# control_FET.net
KiCad netlist of a schematic drawn in EAGLE
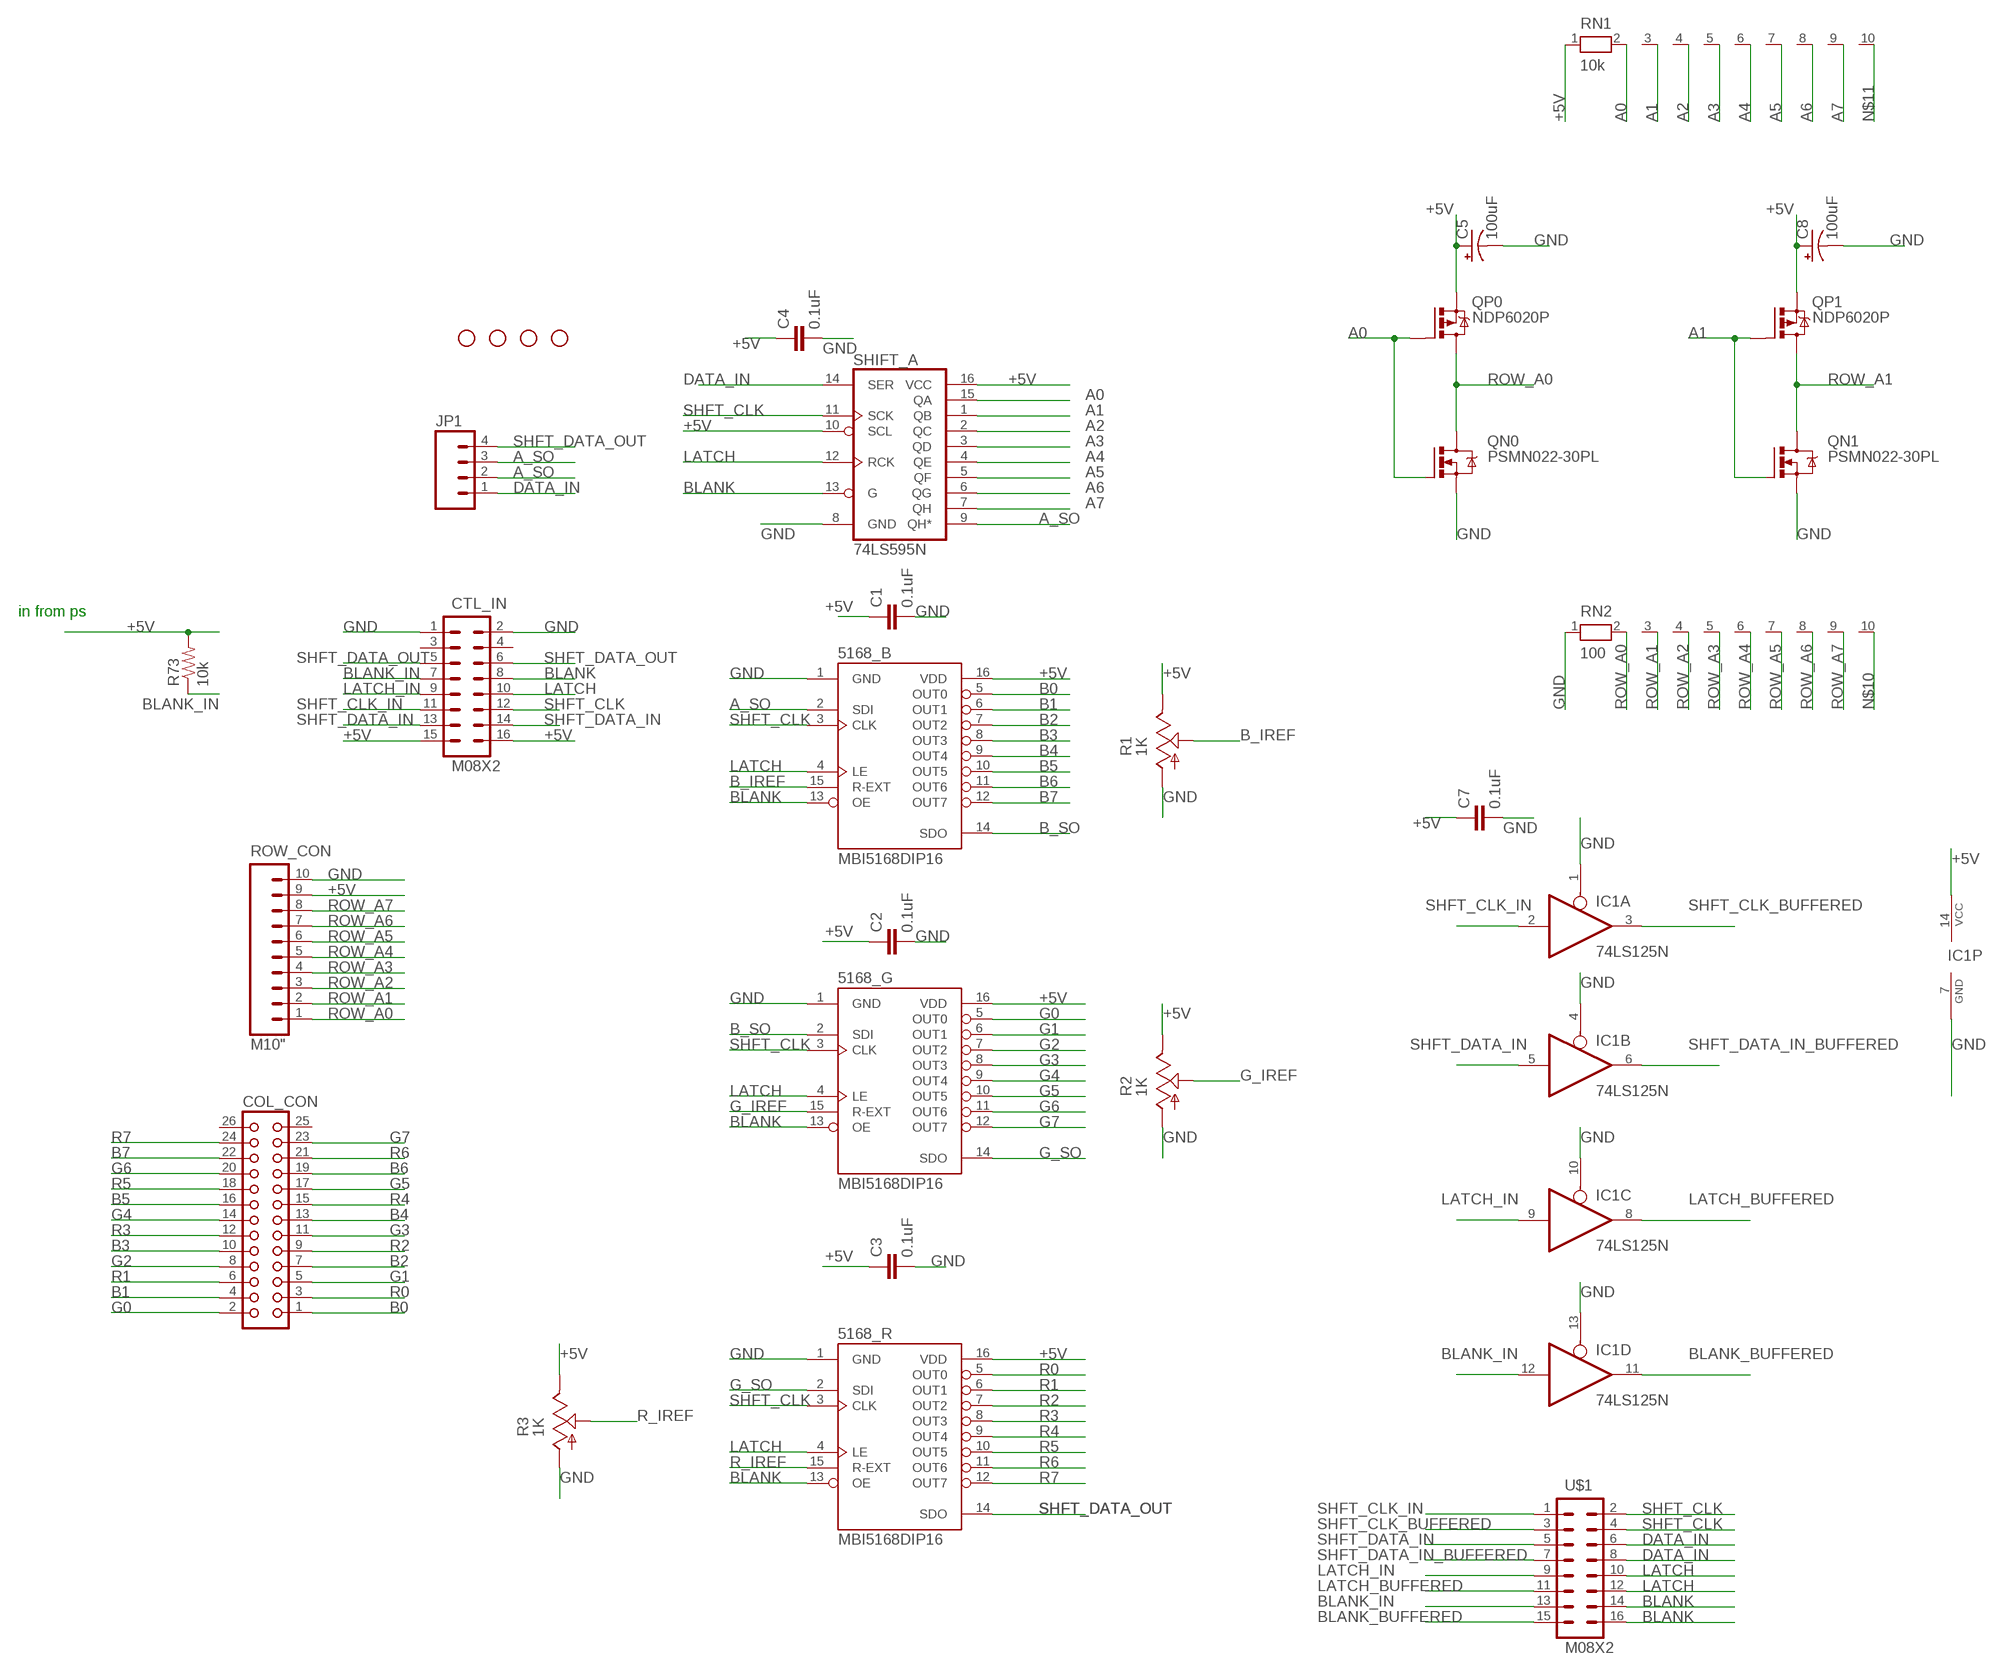
[diagram p0: schematic, sheet 1, part 1 of 2]
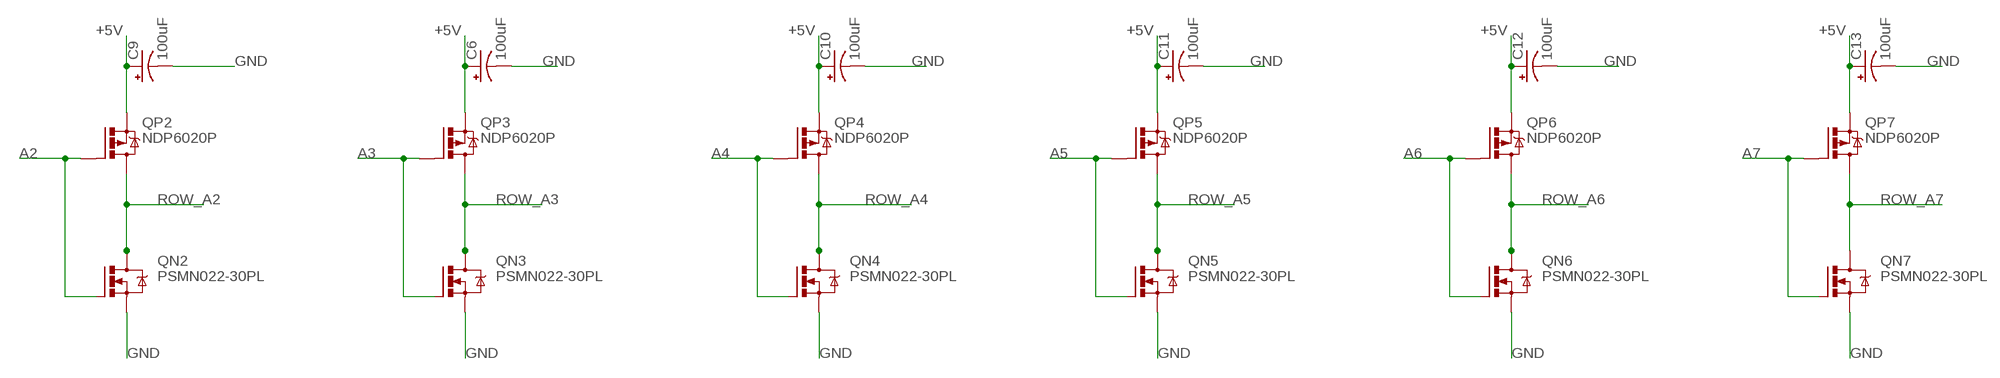
[diagram p1: schematic, sheet 1, part 2 of 2]

(export (version "E")
  (design (tool "Eeschema 10.0.6"))
  (components
    (comp (ref "5168_B")
      (value "MBI5168DIP16")
      (footprint "eagle-import:DIL16")
      (libsource (lib "eagle-import") (part "MBI5168DIP16"))
    )
    (comp (ref "5168_G")
      (value "MBI5168DIP16")
      (footprint "eagle-import:DIL16")
      (libsource (lib "eagle-import") (part "MBI5168DIP16"))
    )
    (comp (ref "5168_R")
      (value "MBI5168DIP16")
      (footprint "eagle-import:DIL16")
      (libsource (lib "eagle-import") (part "MBI5168DIP16"))
    )
    (comp (ref "C1")
      (value "0.1uF")
      (footprint "eagle-import:C2.5-3")
      (libsource (lib "eagle-import") (part "C2,5-3"))
    )
    (comp (ref "C2")
      (value "0.1uF")
      (footprint "eagle-import:C2.5-3")
      (libsource (lib "eagle-import") (part "C2,5-3"))
    )
    (comp (ref "C3")
      (value "0.1uF")
      (footprint "eagle-import:C2.5-3")
      (libsource (lib "eagle-import") (part "C2,5-3"))
    )
    (comp (ref "C4")
      (value "0.1uF")
      (footprint "eagle-import:C2.5-3")
      (libsource (lib "eagle-import") (part "C2,5-3"))
    )
    (comp (ref "C5")
      (value "100uF")
      (footprint "eagle-import:CPOL-RADIAL-100UF-25V")
      (libsource (lib "eagle-import") (part "CAP_POLPTH1"))
    )
    (comp (ref "C6")
      (value "100uF")
      (footprint "eagle-import:CPOL-RADIAL-100UF-25V")
      (libsource (lib "eagle-import") (part "CAP_POLPTH1"))
    )
    (comp (ref "C7")
      (value "0.1uF")
      (footprint "eagle-import:C2.5-3")
      (libsource (lib "eagle-import") (part "C2,5-3"))
    )
    (comp (ref "C8")
      (value "100uF")
      (footprint "eagle-import:CPOL-RADIAL-100UF-25V")
      (libsource (lib "eagle-import") (part "CAP_POLPTH1"))
    )
    (comp (ref "C9")
      (value "100uF")
      (footprint "eagle-import:CPOL-RADIAL-100UF-25V")
      (libsource (lib "eagle-import") (part "CAP_POLPTH1"))
    )
    (comp (ref "C10")
      (value "100uF")
      (footprint "eagle-import:CPOL-RADIAL-100UF-25V")
      (libsource (lib "eagle-import") (part "CAP_POLPTH1"))
    )
    (comp (ref "C11")
      (value "100uF")
      (footprint "eagle-import:CPOL-RADIAL-100UF-25V")
      (libsource (lib "eagle-import") (part "CAP_POLPTH1"))
    )
    (comp (ref "C12")
      (value "100uF")
      (footprint "eagle-import:CPOL-RADIAL-100UF-25V")
      (libsource (lib "eagle-import") (part "CAP_POLPTH1"))
    )
    (comp (ref "C13")
      (value "100uF")
      (footprint "eagle-import:CPOL-RADIAL-100UF-25V")
      (libsource (lib "eagle-import") (part "CAP_POLPTH1"))
    )
    (comp (ref "COL_CON")
      (value "CON26")
      (footprint "eagle-import:CON26")
      (libsource (lib "eagle-import") (part "CON26"))
    )
    (comp (ref "CTL_IN")
      (value "M08X2")
      (footprint "eagle-import:2X8")
      (libsource (lib "eagle-import") (part "M08X2"))
    )
    (comp (ref "IC1")
      (value "74LS125N")
      (footprint "eagle-import:DIL14")
      (libsource (lib "eagle-import") (part "74125NLS"))
    )
    (comp (ref "JP1")
      (value "M04PTH")
      (footprint "eagle-import:1X04")
      (libsource (lib "eagle-import") (part "M04PTH"))
    )
    (comp (ref "QN0")
      (value "PSMN022-30PL")
      (footprint "eagle-import:TO220BV")
      (libsource (lib "eagle-import") (part "IRF520"))
    )
    (comp (ref "QN1")
      (value "PSMN022-30PL")
      (footprint "eagle-import:TO220BV")
      (libsource (lib "eagle-import") (part "IRF520"))
    )
    (comp (ref "QN2")
      (value "PSMN022-30PL")
      (footprint "eagle-import:TO220BV")
      (libsource (lib "eagle-import") (part "IRF520"))
    )
    (comp (ref "QN3")
      (value "PSMN022-30PL")
      (footprint "eagle-import:TO220BV")
      (libsource (lib "eagle-import") (part "IRF520"))
    )
    (comp (ref "QN4")
      (value "PSMN022-30PL")
      (footprint "eagle-import:TO220BV")
      (libsource (lib "eagle-import") (part "IRF520"))
    )
    (comp (ref "QN5")
      (value "PSMN022-30PL")
      (footprint "eagle-import:TO220BV")
      (libsource (lib "eagle-import") (part "IRF520"))
    )
    (comp (ref "QN6")
      (value "PSMN022-30PL")
      (footprint "eagle-import:TO220BV")
      (libsource (lib "eagle-import") (part "IRF520"))
    )
    (comp (ref "QN7")
      (value "PSMN022-30PL")
      (footprint "eagle-import:TO220BV")
      (libsource (lib "eagle-import") (part "IRF520"))
    )
    (comp (ref "QP0")
      (value "NDP6020P")
      (footprint "eagle-import:TO220BV")
      (libsource (lib "eagle-import") (part "IRF9530"))
    )
    (comp (ref "QP1")
      (value "NDP6020P")
      (footprint "eagle-import:TO220BV")
      (libsource (lib "eagle-import") (part "IRF9530"))
    )
    (comp (ref "QP2")
      (value "NDP6020P")
      (footprint "eagle-import:TO220BV")
      (libsource (lib "eagle-import") (part "IRF9530"))
    )
    (comp (ref "QP3")
      (value "NDP6020P")
      (footprint "eagle-import:TO220BV")
      (libsource (lib "eagle-import") (part "IRF9530"))
    )
    (comp (ref "QP4")
      (value "NDP6020P")
      (footprint "eagle-import:TO220BV")
      (libsource (lib "eagle-import") (part "IRF9530"))
    )
    (comp (ref "QP5")
      (value "NDP6020P")
      (footprint "eagle-import:TO220BV")
      (libsource (lib "eagle-import") (part "IRF9530"))
    )
    (comp (ref "QP6")
      (value "NDP6020P")
      (footprint "eagle-import:TO220BV")
      (libsource (lib "eagle-import") (part "IRF9530"))
    )
    (comp (ref "QP7")
      (value "NDP6020P")
      (footprint "eagle-import:TO220BV")
      (libsource (lib "eagle-import") (part "IRF9530"))
    )
    (comp (ref "R1")
      (value "1K")
      (footprint "eagle-import:CA6V")
      (libsource (lib "eagle-import") (part "TRIM_US-CA6V"))
    )
    (comp (ref "R2")
      (value "1K")
      (footprint "eagle-import:CA6V")
      (libsource (lib "eagle-import") (part "TRIM_US-CA6V"))
    )
    (comp (ref "R3")
      (value "1K")
      (footprint "eagle-import:CA6V")
      (libsource (lib "eagle-import") (part "TRIM_US-CA6V"))
    )
    (comp (ref "R73")
      (value "10k")
      (footprint "eagle-import:0207_10")
      (libsource (lib "eagle-import") (part "R-US_0207/10"))
    )
    (comp (ref "RN1")
      (value "10k")
      (footprint "eagle-import:RN-10")
      (libsource (lib "eagle-import") (part "RN09"))
    )
    (comp (ref "RN2")
      (value "100")
      (footprint "eagle-import:RN-10")
      (libsource (lib "eagle-import") (part "RN09"))
    )
    (comp (ref "ROW_CON")
      (value "M10\"")
      (footprint "eagle-import:1X10")
      (libsource (lib "eagle-import") (part "M10{dblquote}"))
    )
    (comp (ref "SHIFT_A")
      (value "74LS595N")
      (footprint "eagle-import:DIL16")
      (libsource (lib "eagle-import") (part "74595NLS"))
    )
    (comp (ref "STANDOFF1")
      (value "STAND-OFF")
      (footprint "eagle-import:STAND-OFF")
      (libsource (lib "eagle-import") (part "STAND-OFF"))
    )
    (comp (ref "STANDOFF2")
      (value "STAND-OFF")
      (footprint "eagle-import:STAND-OFF")
      (libsource (lib "eagle-import") (part "STAND-OFF"))
    )
    (comp (ref "STANDOFF3")
      (value "STAND-OFF")
      (footprint "eagle-import:STAND-OFF")
      (libsource (lib "eagle-import") (part "STAND-OFF"))
    )
    (comp (ref "STANDOFF4")
      (value "STAND-OFF")
      (footprint "eagle-import:STAND-OFF")
      (libsource (lib "eagle-import") (part "STAND-OFF"))
    )
    (comp (ref "U$1")
      (value "M08X2")
      (footprint "eagle-import:2X8")
      (libsource (lib "eagle-import") (part "M08X2"))
    )
  )
  (nets
    (net (code "1") (name "/+5V") (class "Default")
      (node (ref "5168_B") (pin "16") (pinfunction "VDD_16") (pintype "power_in"))
      (node (ref "5168_G") (pin "16") (pinfunction "VDD_16") (pintype "power_in"))
      (node (ref "5168_R") (pin "16") (pinfunction "VDD_16") (pintype "power_in"))
      (node (ref "C1") (pin "1") (pinfunction "1_1") (pintype "passive"))
      (node (ref "C10") (pin "1") (pinfunction "+_1") (pintype "passive"))
      (node (ref "C11") (pin "1") (pinfunction "+_1") (pintype "passive"))
      (node (ref "C12") (pin "1") (pinfunction "+_1") (pintype "passive"))
      (node (ref "C13") (pin "1") (pinfunction "+_1") (pintype "passive"))
      (node (ref "C2") (pin "1") (pinfunction "1_1") (pintype "passive"))
      (node (ref "C3") (pin "1") (pinfunction "1_1") (pintype "passive"))
      (node (ref "C4") (pin "1") (pinfunction "1_1") (pintype "passive"))
      (node (ref "C5") (pin "1") (pinfunction "+_1") (pintype "passive"))
      (node (ref "C6") (pin "1") (pinfunction "+_1") (pintype "passive"))
      (node (ref "C7") (pin "1") (pinfunction "1_1") (pintype "passive"))
      (node (ref "C8") (pin "1") (pinfunction "+_1") (pintype "passive"))
      (node (ref "C9") (pin "1") (pinfunction "+_1") (pintype "passive"))
      (node (ref "CTL_IN") (pin "15") (pinfunction "15_15") (pintype "passive"))
      (node (ref "CTL_IN") (pin "16") (pinfunction "16_16") (pintype "passive"))
      (node (ref "IC1") (pin "14") (pinfunction "VCC_14") (pintype "power_in"))
      (node (ref "QP0") (pin "S") (pinfunction "S_S") (pintype "passive"))
      (node (ref "QP1") (pin "S") (pinfunction "S_S") (pintype "passive"))
      (node (ref "QP2") (pin "S") (pinfunction "S_S") (pintype "passive"))
      (node (ref "QP3") (pin "S") (pinfunction "S_S") (pintype "passive"))
      (node (ref "QP4") (pin "S") (pinfunction "S_S") (pintype "passive"))
      (node (ref "QP5") (pin "S") (pinfunction "S_S") (pintype "passive"))
      (node (ref "QP6") (pin "S") (pinfunction "S_S") (pintype "passive"))
      (node (ref "QP7") (pin "S") (pinfunction "S_S") (pintype "passive"))
      (node (ref "R1") (pin "E") (pinfunction "E_E") (pintype "passive"))
      (node (ref "R2") (pin "E") (pinfunction "E_E") (pintype "passive"))
      (node (ref "R3") (pin "E") (pinfunction "E_E") (pintype "passive"))
      (node (ref "R73") (pin "2") (pinfunction "2_2") (pintype "passive"))
      (node (ref "RN1") (pin "1") (pinfunction "1_1") (pintype "passive"))
      (node (ref "ROW_CON") (pin "9") (pinfunction "9_9") (pintype "passive"))
      (node (ref "SHIFT_A") (pin "10") (pinfunction "SCL_10") (pintype "input"))
      (node (ref "SHIFT_A") (pin "16") (pinfunction "VCC_16") (pintype "power_in"))
    )
    (net (code "2") (name "/A0") (class "Default")
      (node (ref "QN0") (pin "G") (pinfunction "G_G") (pintype "passive"))
      (node (ref "QP0") (pin "G") (pinfunction "G_G") (pintype "passive"))
      (node (ref "RN1") (pin "2") (pinfunction "2_2") (pintype "passive"))
      (node (ref "SHIFT_A") (pin "15") (pinfunction "QA_15") (pintype "tri_state"))
    )
    (net (code "3") (name "/A1") (class "Default")
      (node (ref "QN1") (pin "G") (pinfunction "G_G") (pintype "passive"))
      (node (ref "QP1") (pin "G") (pinfunction "G_G") (pintype "passive"))
      (node (ref "RN1") (pin "3") (pinfunction "3_3") (pintype "passive"))
      (node (ref "SHIFT_A") (pin "1") (pinfunction "QB_1") (pintype "tri_state"))
    )
    (net (code "4") (name "/A2") (class "Default")
      (node (ref "QN2") (pin "G") (pinfunction "G_G") (pintype "passive"))
      (node (ref "QP2") (pin "G") (pinfunction "G_G") (pintype "passive"))
      (node (ref "RN1") (pin "4") (pinfunction "4_4") (pintype "passive"))
      (node (ref "SHIFT_A") (pin "2") (pinfunction "QC_2") (pintype "tri_state"))
    )
    (net (code "5") (name "/A3") (class "Default")
      (node (ref "QN3") (pin "G") (pinfunction "G_G") (pintype "passive"))
      (node (ref "QP3") (pin "G") (pinfunction "G_G") (pintype "passive"))
      (node (ref "RN1") (pin "5") (pinfunction "5_5") (pintype "passive"))
      (node (ref "SHIFT_A") (pin "3") (pinfunction "QD_3") (pintype "tri_state"))
    )
    (net (code "6") (name "/A4") (class "Default")
      (node (ref "QN4") (pin "G") (pinfunction "G_G") (pintype "passive"))
      (node (ref "QP4") (pin "G") (pinfunction "G_G") (pintype "passive"))
      (node (ref "RN1") (pin "6") (pinfunction "6_6") (pintype "passive"))
      (node (ref "SHIFT_A") (pin "4") (pinfunction "QE_4") (pintype "tri_state"))
    )
    (net (code "7") (name "/A5") (class "Default")
      (node (ref "QN5") (pin "G") (pinfunction "G_G") (pintype "passive"))
      (node (ref "QP5") (pin "G") (pinfunction "G_G") (pintype "passive"))
      (node (ref "RN1") (pin "7") (pinfunction "7_7") (pintype "passive"))
      (node (ref "SHIFT_A") (pin "5") (pinfunction "QF_5") (pintype "tri_state"))
    )
    (net (code "8") (name "/A6") (class "Default")
      (node (ref "QN6") (pin "G") (pinfunction "G_G") (pintype "passive"))
      (node (ref "QP6") (pin "G") (pinfunction "G_G") (pintype "passive"))
      (node (ref "RN1") (pin "8") (pinfunction "8_8") (pintype "passive"))
      (node (ref "SHIFT_A") (pin "6") (pinfunction "QG_6") (pintype "tri_state"))
    )
    (net (code "9") (name "/A7") (class "Default")
      (node (ref "QN7") (pin "G") (pinfunction "G_G") (pintype "passive"))
      (node (ref "QP7") (pin "G") (pinfunction "G_G") (pintype "passive"))
      (node (ref "RN1") (pin "9") (pinfunction "9_9") (pintype "passive"))
      (node (ref "SHIFT_A") (pin "7") (pinfunction "QH_7") (pintype "tri_state"))
    )
    (net (code "10") (name "/A_SO") (class "Default")
      (node (ref "5168_B") (pin "2") (pinfunction "SDI_2") (pintype "input"))
      (node (ref "JP1") (pin "2") (pinfunction "2_2") (pintype "passive"))
      (node (ref "JP1") (pin "3") (pinfunction "3_3") (pintype "passive"))
      (node (ref "SHIFT_A") (pin "9") (pinfunction "QH*_9") (pintype "tri_state"))
    )
    (net (code "11") (name "/B0") (class "Default")
      (node (ref "5168_B") (pin "5") (pinfunction "OUT0_5") (pintype "output"))
      (node (ref "COL_CON") (pin "1") (pinfunction "1_1") (pintype "passive"))
    )
    (net (code "12") (name "/B1") (class "Default")
      (node (ref "5168_B") (pin "6") (pinfunction "OUT1_6") (pintype "output"))
      (node (ref "COL_CON") (pin "4") (pinfunction "4_4") (pintype "passive"))
    )
    (net (code "13") (name "/B2") (class "Default")
      (node (ref "5168_B") (pin "7") (pinfunction "OUT2_7") (pintype "output"))
      (node (ref "COL_CON") (pin "7") (pinfunction "7_7") (pintype "passive"))
    )
    (net (code "14") (name "/B3") (class "Default")
      (node (ref "5168_B") (pin "8") (pinfunction "OUT3_8") (pintype "output"))
      (node (ref "COL_CON") (pin "10") (pinfunction "10_10") (pintype "passive"))
    )
    (net (code "15") (name "/B4") (class "Default")
      (node (ref "5168_B") (pin "9") (pinfunction "OUT4_9") (pintype "output"))
      (node (ref "COL_CON") (pin "13") (pinfunction "13_13") (pintype "passive"))
    )
    (net (code "16") (name "/B5") (class "Default")
      (node (ref "5168_B") (pin "10") (pinfunction "OUT5_10") (pintype "output"))
      (node (ref "COL_CON") (pin "16") (pinfunction "16_16") (pintype "passive"))
    )
    (net (code "17") (name "/B6") (class "Default")
      (node (ref "5168_B") (pin "11") (pinfunction "OUT6_11") (pintype "output"))
      (node (ref "COL_CON") (pin "19") (pinfunction "19_19") (pintype "passive"))
    )
    (net (code "18") (name "/B7") (class "Default")
      (node (ref "5168_B") (pin "12") (pinfunction "OUT7_12") (pintype "output"))
      (node (ref "COL_CON") (pin "22") (pinfunction "22_22") (pintype "passive"))
    )
    (net (code "19") (name "/BLANK") (class "Default")
      (node (ref "5168_B") (pin "13") (pinfunction "OE_13") (pintype "input"))
      (node (ref "5168_G") (pin "13") (pinfunction "OE_13") (pintype "input"))
      (node (ref "5168_R") (pin "13") (pinfunction "OE_13") (pintype "input"))
      (node (ref "CTL_IN") (pin "8") (pinfunction "8_8") (pintype "passive"))
      (node (ref "SHIFT_A") (pin "13") (pinfunction "G_13") (pintype "input"))
      (node (ref "U$1") (pin "14") (pinfunction "14_14") (pintype "passive"))
      (node (ref "U$1") (pin "16") (pinfunction "16_16") (pintype "passive"))
    )
    (net (code "20") (name "/BLANK_BUFFERED") (class "Default")
      (node (ref "IC1") (pin "11") (pinfunction "O_11") (pintype "tri_state"))
      (node (ref "U$1") (pin "15") (pinfunction "15_15") (pintype "passive"))
    )
    (net (code "21") (name "/BLANK_IN") (class "Default")
      (node (ref "CTL_IN") (pin "7") (pinfunction "7_7") (pintype "passive"))
      (node (ref "IC1") (pin "12") (pinfunction "I_12") (pintype "input"))
      (node (ref "R73") (pin "1") (pinfunction "1_1") (pintype "passive"))
      (node (ref "U$1") (pin "13") (pinfunction "13_13") (pintype "passive"))
    )
    (net (code "22") (name "/B_IREF") (class "Default")
      (node (ref "5168_B") (pin "15") (pinfunction "R-EXT_15") (pintype "input"))
      (node (ref "R1") (pin "S") (pinfunction "S_S") (pintype "passive"))
    )
    (net (code "23") (name "/B_SO") (class "Default")
      (node (ref "5168_B") (pin "14") (pinfunction "SDO_14") (pintype "output"))
      (node (ref "5168_G") (pin "2") (pinfunction "SDI_2") (pintype "input"))
    )
    (net (code "24") (name "/DATA_IN") (class "Default")
      (node (ref "JP1") (pin "1") (pinfunction "1_1") (pintype "passive"))
      (node (ref "SHIFT_A") (pin "14") (pinfunction "SER_14") (pintype "input"))
      (node (ref "U$1") (pin "6") (pinfunction "6_6") (pintype "passive"))
      (node (ref "U$1") (pin "8") (pinfunction "8_8") (pintype "passive"))
    )
    (net (code "25") (name "/G0") (class "Default")
      (node (ref "5168_G") (pin "5") (pinfunction "OUT0_5") (pintype "output"))
      (node (ref "COL_CON") (pin "2") (pinfunction "2_2") (pintype "passive"))
    )
    (net (code "26") (name "/G1") (class "Default")
      (node (ref "5168_G") (pin "6") (pinfunction "OUT1_6") (pintype "output"))
      (node (ref "COL_CON") (pin "5") (pinfunction "5_5") (pintype "passive"))
    )
    (net (code "27") (name "/G2") (class "Default")
      (node (ref "5168_G") (pin "7") (pinfunction "OUT2_7") (pintype "output"))
      (node (ref "COL_CON") (pin "8") (pinfunction "8_8") (pintype "passive"))
    )
    (net (code "28") (name "/G3") (class "Default")
      (node (ref "5168_G") (pin "8") (pinfunction "OUT3_8") (pintype "output"))
      (node (ref "COL_CON") (pin "11") (pinfunction "11_11") (pintype "passive"))
    )
    (net (code "29") (name "/G4") (class "Default")
      (node (ref "5168_G") (pin "9") (pinfunction "OUT4_9") (pintype "output"))
      (node (ref "COL_CON") (pin "14") (pinfunction "14_14") (pintype "passive"))
    )
    (net (code "30") (name "/G5") (class "Default")
      (node (ref "5168_G") (pin "10") (pinfunction "OUT5_10") (pintype "output"))
      (node (ref "COL_CON") (pin "17") (pinfunction "17_17") (pintype "passive"))
    )
    (net (code "31") (name "/G6") (class "Default")
      (node (ref "5168_G") (pin "11") (pinfunction "OUT6_11") (pintype "output"))
      (node (ref "COL_CON") (pin "20") (pinfunction "20_20") (pintype "passive"))
    )
    (net (code "32") (name "/G7") (class "Default")
      (node (ref "5168_G") (pin "12") (pinfunction "OUT7_12") (pintype "output"))
      (node (ref "COL_CON") (pin "23") (pinfunction "23_23") (pintype "passive"))
    )
    (net (code "33") (name "/GND") (class "Default")
      (node (ref "5168_B") (pin "1") (pinfunction "GND_1") (pintype "power_in"))
      (node (ref "5168_G") (pin "1") (pinfunction "GND_1") (pintype "power_in"))
      (node (ref "5168_R") (pin "1") (pinfunction "GND_1") (pintype "power_in"))
      (node (ref "C1") (pin "2") (pinfunction "2_2") (pintype "passive"))
      (node (ref "C10") (pin "2") (pinfunction "-_2") (pintype "passive"))
      (node (ref "C11") (pin "2") (pinfunction "-_2") (pintype "passive"))
      (node (ref "C12") (pin "2") (pinfunction "-_2") (pintype "passive"))
      (node (ref "C13") (pin "2") (pinfunction "-_2") (pintype "passive"))
      (node (ref "C2") (pin "2") (pinfunction "2_2") (pintype "passive"))
      (node (ref "C3") (pin "2") (pinfunction "2_2") (pintype "passive"))
      (node (ref "C4") (pin "2") (pinfunction "2_2") (pintype "passive"))
      (node (ref "C5") (pin "2") (pinfunction "-_2") (pintype "passive"))
      (node (ref "C6") (pin "2") (pinfunction "-_2") (pintype "passive"))
      (node (ref "C7") (pin "2") (pinfunction "2_2") (pintype "passive"))
      (node (ref "C8") (pin "2") (pinfunction "-_2") (pintype "passive"))
      (node (ref "C9") (pin "2") (pinfunction "-_2") (pintype "passive"))
      (node (ref "CTL_IN") (pin "1") (pinfunction "1_1") (pintype "passive"))
      (node (ref "CTL_IN") (pin "2") (pinfunction "2_2") (pintype "passive"))
      (node (ref "IC1") (pin "1") (pinfunction "OE_1") (pintype "input"))
      (node (ref "IC1") (pin "10") (pinfunction "OE_10") (pintype "input"))
      (node (ref "IC1") (pin "13") (pinfunction "OE_13") (pintype "input"))
      (node (ref "IC1") (pin "4") (pinfunction "OE_4") (pintype "input"))
      (node (ref "IC1") (pin "7") (pinfunction "GND_7") (pintype "power_in"))
      (node (ref "QN0") (pin "S") (pinfunction "S_S") (pintype "passive"))
      (node (ref "QN1") (pin "S") (pinfunction "S_S") (pintype "passive"))
      (node (ref "QN2") (pin "S") (pinfunction "S_S") (pintype "passive"))
      (node (ref "QN3") (pin "S") (pinfunction "S_S") (pintype "passive"))
      (node (ref "QN4") (pin "S") (pinfunction "S_S") (pintype "passive"))
      (node (ref "QN5") (pin "S") (pinfunction "S_S") (pintype "passive"))
      (node (ref "QN6") (pin "S") (pinfunction "S_S") (pintype "passive"))
      (node (ref "QN7") (pin "S") (pinfunction "S_S") (pintype "passive"))
      (node (ref "R1") (pin "A") (pinfunction "A_A") (pintype "passive"))
      (node (ref "R2") (pin "A") (pinfunction "A_A") (pintype "passive"))
      (node (ref "R3") (pin "A") (pinfunction "A_A") (pintype "passive"))
      (node (ref "RN2") (pin "1") (pinfunction "1_1") (pintype "passive"))
      (node (ref "ROW_CON") (pin "10") (pinfunction "10_10") (pintype "passive"))
      (node (ref "SHIFT_A") (pin "8") (pinfunction "GND_8") (pintype "power_in"))
    )
    (net (code "34") (name "/G_IREF") (class "Default")
      (node (ref "5168_G") (pin "15") (pinfunction "R-EXT_15") (pintype "input"))
      (node (ref "R2") (pin "S") (pinfunction "S_S") (pintype "passive"))
    )
    (net (code "35") (name "/G_SO") (class "Default")
      (node (ref "5168_G") (pin "14") (pinfunction "SDO_14") (pintype "output"))
      (node (ref "5168_R") (pin "2") (pinfunction "SDI_2") (pintype "input"))
    )
    (net (code "36") (name "/LATCH") (class "Default")
      (node (ref "5168_B") (pin "4") (pinfunction "LE_4") (pintype "input"))
      (node (ref "5168_G") (pin "4") (pinfunction "LE_4") (pintype "input"))
      (node (ref "5168_R") (pin "4") (pinfunction "LE_4") (pintype "input"))
      (node (ref "CTL_IN") (pin "10") (pinfunction "10_10") (pintype "passive"))
      (node (ref "SHIFT_A") (pin "12") (pinfunction "RCK_12") (pintype "input"))
      (node (ref "U$1") (pin "10") (pinfunction "10_10") (pintype "passive"))
      (node (ref "U$1") (pin "12") (pinfunction "12_12") (pintype "passive"))
    )
    (net (code "37") (name "/LATCH_BUFFERED") (class "Default")
      (node (ref "IC1") (pin "8") (pinfunction "O_8") (pintype "tri_state"))
      (node (ref "U$1") (pin "11") (pinfunction "11_11") (pintype "passive"))
    )
    (net (code "38") (name "/LATCH_IN") (class "Default")
      (node (ref "CTL_IN") (pin "9") (pinfunction "9_9") (pintype "passive"))
      (node (ref "IC1") (pin "9") (pinfunction "I_9") (pintype "input"))
      (node (ref "U$1") (pin "9") (pinfunction "9_9") (pintype "passive"))
    )
    (net (code "39") (name "/N$10") (class "Default")
      (node (ref "RN2") (pin "10") (pinfunction "10_10") (pintype "passive"))
    )
    (net (code "40") (name "/N$11") (class "Default")
      (node (ref "RN1") (pin "10") (pinfunction "10_10") (pintype "passive"))
    )
    (net (code "41") (name "/R0") (class "Default")
      (node (ref "5168_R") (pin "5") (pinfunction "OUT0_5") (pintype "output"))
      (node (ref "COL_CON") (pin "3") (pinfunction "3_3") (pintype "passive"))
    )
    (net (code "42") (name "/R1") (class "Default")
      (node (ref "5168_R") (pin "6") (pinfunction "OUT1_6") (pintype "output"))
      (node (ref "COL_CON") (pin "6") (pinfunction "6_6") (pintype "passive"))
    )
    (net (code "43") (name "/R2") (class "Default")
      (node (ref "5168_R") (pin "7") (pinfunction "OUT2_7") (pintype "output"))
      (node (ref "COL_CON") (pin "9") (pinfunction "9_9") (pintype "passive"))
    )
    (net (code "44") (name "/R3") (class "Default")
      (node (ref "5168_R") (pin "8") (pinfunction "OUT3_8") (pintype "output"))
      (node (ref "COL_CON") (pin "12") (pinfunction "12_12") (pintype "passive"))
    )
    (net (code "45") (name "/R4") (class "Default")
      (node (ref "5168_R") (pin "9") (pinfunction "OUT4_9") (pintype "output"))
      (node (ref "COL_CON") (pin "15") (pinfunction "15_15") (pintype "passive"))
    )
    (net (code "46") (name "/R5") (class "Default")
      (node (ref "5168_R") (pin "10") (pinfunction "OUT5_10") (pintype "output"))
      (node (ref "COL_CON") (pin "18") (pinfunction "18_18") (pintype "passive"))
    )
    (net (code "47") (name "/R6") (class "Default")
      (node (ref "5168_R") (pin "11") (pinfunction "OUT6_11") (pintype "output"))
      (node (ref "COL_CON") (pin "21") (pinfunction "21_21") (pintype "passive"))
    )
    (net (code "48") (name "/R7") (class "Default")
      (node (ref "5168_R") (pin "12") (pinfunction "OUT7_12") (pintype "output"))
      (node (ref "COL_CON") (pin "24") (pinfunction "24_24") (pintype "passive"))
    )
    (net (code "49") (name "/ROW_A0") (class "Default")
      (node (ref "QN0") (pin "D") (pinfunction "D_D") (pintype "passive"))
      (node (ref "QP0") (pin "D") (pinfunction "D_D") (pintype "passive"))
      (node (ref "RN2") (pin "2") (pinfunction "2_2") (pintype "passive"))
      (node (ref "ROW_CON") (pin "1") (pinfunction "1_1") (pintype "passive"))
    )
    (net (code "50") (name "/ROW_A1") (class "Default")
      (node (ref "QN1") (pin "D") (pinfunction "D_D") (pintype "passive"))
      (node (ref "QP1") (pin "D") (pinfunction "D_D") (pintype "passive"))
      (node (ref "RN2") (pin "3") (pinfunction "3_3") (pintype "passive"))
      (node (ref "ROW_CON") (pin "2") (pinfunction "2_2") (pintype "passive"))
    )
    (net (code "51") (name "/ROW_A2") (class "Default")
      (node (ref "QN2") (pin "D") (pinfunction "D_D") (pintype "passive"))
      (node (ref "QP2") (pin "D") (pinfunction "D_D") (pintype "passive"))
      (node (ref "RN2") (pin "4") (pinfunction "4_4") (pintype "passive"))
      (node (ref "ROW_CON") (pin "3") (pinfunction "3_3") (pintype "passive"))
    )
    (net (code "52") (name "/ROW_A3") (class "Default")
      (node (ref "QN3") (pin "D") (pinfunction "D_D") (pintype "passive"))
      (node (ref "QP3") (pin "D") (pinfunction "D_D") (pintype "passive"))
      (node (ref "RN2") (pin "5") (pinfunction "5_5") (pintype "passive"))
      (node (ref "ROW_CON") (pin "4") (pinfunction "4_4") (pintype "passive"))
    )
    (net (code "53") (name "/ROW_A4") (class "Default")
      (node (ref "QN4") (pin "D") (pinfunction "D_D") (pintype "passive"))
      (node (ref "QP4") (pin "D") (pinfunction "D_D") (pintype "passive"))
      (node (ref "RN2") (pin "6") (pinfunction "6_6") (pintype "passive"))
      (node (ref "ROW_CON") (pin "5") (pinfunction "5_5") (pintype "passive"))
    )
    (net (code "54") (name "/ROW_A5") (class "Default")
      (node (ref "QN5") (pin "D") (pinfunction "D_D") (pintype "passive"))
      (node (ref "QP5") (pin "D") (pinfunction "D_D") (pintype "passive"))
      (node (ref "RN2") (pin "7") (pinfunction "7_7") (pintype "passive"))
      (node (ref "ROW_CON") (pin "6") (pinfunction "6_6") (pintype "passive"))
    )
    (net (code "55") (name "/ROW_A6") (class "Default")
      (node (ref "QN6") (pin "D") (pinfunction "D_D") (pintype "passive"))
      (node (ref "QP6") (pin "D") (pinfunction "D_D") (pintype "passive"))
      (node (ref "RN2") (pin "8") (pinfunction "8_8") (pintype "passive"))
      (node (ref "ROW_CON") (pin "7") (pinfunction "7_7") (pintype "passive"))
    )
    (net (code "56") (name "/ROW_A7") (class "Default")
      (node (ref "QN7") (pin "D") (pinfunction "D_D") (pintype "passive"))
      (node (ref "QP7") (pin "D") (pinfunction "D_D") (pintype "passive"))
      (node (ref "RN2") (pin "9") (pinfunction "9_9") (pintype "passive"))
      (node (ref "ROW_CON") (pin "8") (pinfunction "8_8") (pintype "passive"))
    )
    (net (code "57") (name "/R_IREF") (class "Default")
      (node (ref "5168_R") (pin "15") (pinfunction "R-EXT_15") (pintype "input"))
      (node (ref "R3") (pin "S") (pinfunction "S_S") (pintype "passive"))
    )
    (net (code "58") (name "/SHFT_CLK") (class "Default")
      (node (ref "5168_B") (pin "3") (pinfunction "CLK_3") (pintype "input"))
      (node (ref "5168_G") (pin "3") (pinfunction "CLK_3") (pintype "input"))
      (node (ref "5168_R") (pin "3") (pinfunction "CLK_3") (pintype "input"))
      (node (ref "CTL_IN") (pin "12") (pinfunction "12_12") (pintype "passive"))
      (node (ref "SHIFT_A") (pin "11") (pinfunction "SCK_11") (pintype "input"))
      (node (ref "U$1") (pin "2") (pinfunction "2_2") (pintype "passive"))
      (node (ref "U$1") (pin "4") (pinfunction "4_4") (pintype "passive"))
    )
    (net (code "59") (name "/SHFT_CLK_BUFFERED") (class "Default")
      (node (ref "IC1") (pin "3") (pinfunction "O_3") (pintype "tri_state"))
      (node (ref "U$1") (pin "3") (pinfunction "3_3") (pintype "passive"))
    )
    (net (code "60") (name "/SHFT_CLK_IN") (class "Default")
      (node (ref "CTL_IN") (pin "11") (pinfunction "11_11") (pintype "passive"))
      (node (ref "IC1") (pin "2") (pinfunction "I_2") (pintype "input"))
      (node (ref "U$1") (pin "1") (pinfunction "1_1") (pintype "passive"))
    )
    (net (code "61") (name "/SHFT_DATA_IN") (class "Default")
      (node (ref "CTL_IN") (pin "13") (pinfunction "13_13") (pintype "passive"))
      (node (ref "CTL_IN") (pin "14") (pinfunction "14_14") (pintype "passive"))
      (node (ref "IC1") (pin "5") (pinfunction "I_5") (pintype "input"))
      (node (ref "U$1") (pin "5") (pinfunction "5_5") (pintype "passive"))
    )
    (net (code "62") (name "/SHFT_DATA_IN_BUFFERED") (class "Default")
      (node (ref "IC1") (pin "6") (pinfunction "O_6") (pintype "tri_state"))
      (node (ref "U$1") (pin "7") (pinfunction "7_7") (pintype "passive"))
    )
    (net (code "63") (name "/SHFT_DATA_OUT") (class "Default")
      (node (ref "5168_R") (pin "14") (pinfunction "SDO_14") (pintype "output"))
      (node (ref "CTL_IN") (pin "5") (pinfunction "5_5") (pintype "passive"))
      (node (ref "CTL_IN") (pin "6") (pinfunction "6_6") (pintype "passive"))
      (node (ref "JP1") (pin "4") (pinfunction "4_4") (pintype "passive"))
    )
    (net (code "64") (name "unconnected-(COL_CON-Pad25)") (class "Default")
      (node (ref "COL_CON") (pin "25") (pinfunction "25_25") (pintype "passive"))
    )
    (net (code "65") (name "unconnected-(COL_CON-Pad26)") (class "Default")
      (node (ref "COL_CON") (pin "26") (pinfunction "26_26") (pintype "passive"))
    )
    (net (code "66") (name "unconnected-(CTL_IN-Pad3)") (class "Default")
      (node (ref "CTL_IN") (pin "3") (pinfunction "3_3") (pintype "passive"))
    )
    (net (code "67") (name "unconnected-(CTL_IN-Pad4)") (class "Default")
      (node (ref "CTL_IN") (pin "4") (pinfunction "4_4") (pintype "passive"))
    )
  )
)
